# PWM.net
KiCad netlist of a schematic drawn in EAGLE
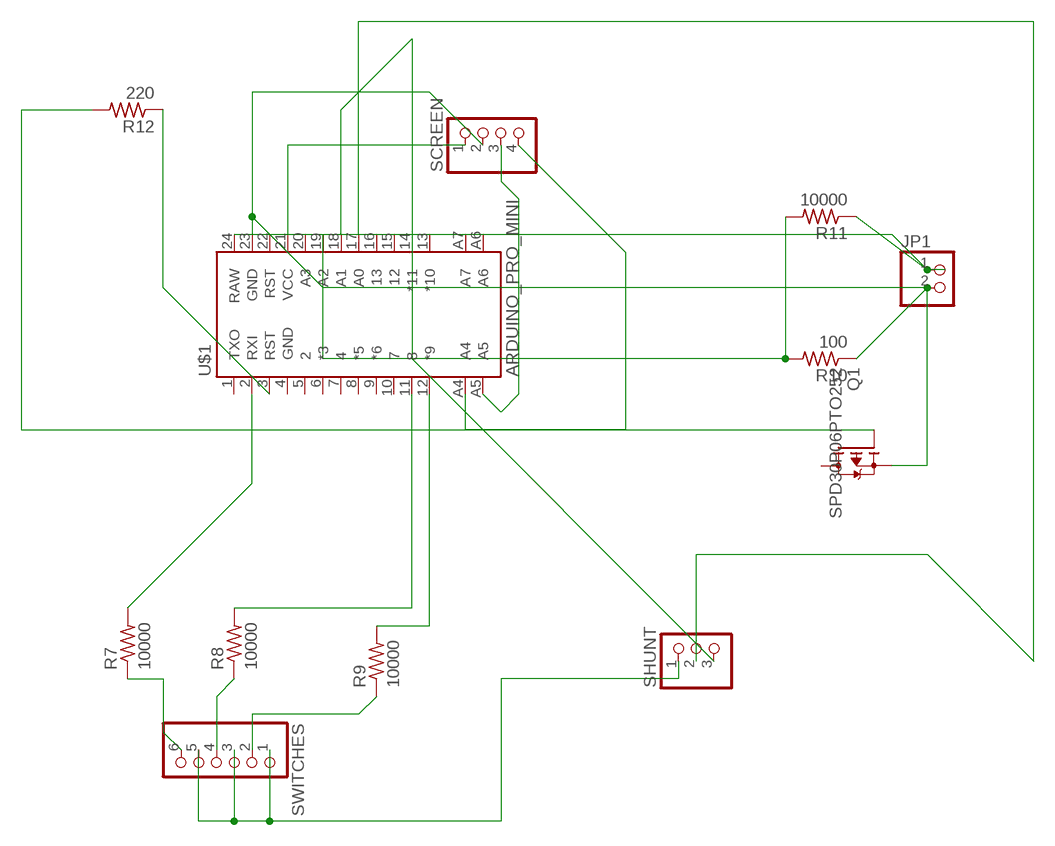
[diagram p0: schematic, sheet 1]

(export (version "E")
  (design (tool "Eeschema 10.0.6"))
  (components
    (comp (ref "JP1")
      (value "PINHD-1X2")
      (footprint "eagle-import:1X02")
      (libsource (lib "eagle-import") (part "PINHD-1X2"))
    )
    (comp (ref "Q1")
      (value "SPD30P06PTO252")
      (footprint "eagle-import:TO252")
      (libsource (lib "eagle-import") (part "SPD30P06PTO252"))
    )
    (comp (ref "R7")
      (value "10000")
      (footprint "eagle-import:0204_7")
      (libsource (lib "eagle-import") (part "R-US_0204/7"))
    )
    (comp (ref "R8")
      (value "10000")
      (footprint "eagle-import:0204_7")
      (libsource (lib "eagle-import") (part "R-US_0204/7"))
    )
    (comp (ref "R9")
      (value "10000")
      (footprint "eagle-import:0204_7")
      (libsource (lib "eagle-import") (part "R-US_0204/7"))
    )
    (comp (ref "R10")
      (value "100")
      (footprint "eagle-import:0204_7")
      (libsource (lib "eagle-import") (part "R-US_0204/7"))
    )
    (comp (ref "R11")
      (value "10000")
      (footprint "eagle-import:0204_7")
      (libsource (lib "eagle-import") (part "R-US_0204/7"))
    )
    (comp (ref "R12")
      (value "220")
      (footprint "eagle-import:0204_7")
      (libsource (lib "eagle-import") (part "R-US_0204/7"))
    )
    (comp (ref "SCREEN")
      (value "PINHD-1X4")
      (footprint "eagle-import:1X04")
      (libsource (lib "eagle-import") (part "PINHD-1X4"))
    )
    (comp (ref "SHUNT")
      (value "PINHD-1X3")
      (footprint "eagle-import:1X03")
      (libsource (lib "eagle-import") (part "PINHD-1X3"))
    )
    (comp (ref "SWITCHES")
      (value "PINHD-1X6")
      (footprint "eagle-import:1X06")
      (libsource (lib "eagle-import") (part "PINHD-1X6"))
    )
    (comp (ref "U$1")
      (value "ARDUINO_PRO_MINI")
      (footprint "eagle-import:ARDUINO_PRO_MINI")
      (libsource (lib "eagle-import") (part "ARDUINO_PRO_MINI"))
    )
  )
  (nets
    (net (code "1") (name "/2") (class "Default")
      (node (ref "R7") (pin "1") (pinfunction "1_1") (pintype "passive"))
      (node (ref "R7") (pin "2") (pinfunction "2_2") (pintype "passive"))
      (node (ref "SWITCHES") (pin "6") (pinfunction "6_6") (pintype "passive"))
      (node (ref "U$1") (pin "2") (pinfunction "RXI_2") (pintype "bidirectional"))
    )
    (net (code "2") (name "/GND") (class "Default")
      (node (ref "JP1") (pin "2") (pinfunction "2_2") (pintype "passive"))
      (node (ref "Q1") (pin "2") (pinfunction "S_2") (pintype "passive"))
      (node (ref "R10") (pin "1") (pinfunction "1_1") (pintype "passive"))
      (node (ref "SCREEN") (pin "2") (pinfunction "2_2") (pintype "passive"))
      (node (ref "SHUNT") (pin "1") (pinfunction "1_1") (pintype "passive"))
      (node (ref "SWITCHES") (pin "1") (pinfunction "1_1") (pintype "passive"))
      (node (ref "SWITCHES") (pin "3") (pinfunction "3_3") (pintype "passive"))
      (node (ref "SWITCHES") (pin "5") (pinfunction "5_5") (pintype "passive"))
      (node (ref "U$1") (pin "23") (pinfunction "GND_23") (pintype "bidirectional"))
    )
    (net (code "3") (name "Net-(Q1-G)") (class "Default")
      (node (ref "Q1") (pin "1") (pinfunction "G_1") (pintype "passive"))
      (node (ref "R12") (pin "2") (pinfunction "2_2") (pintype "passive"))
    )
    (net (code "4") (name "Net-(R8-Pad1)") (class "Default")
      (node (ref "R8") (pin "1") (pinfunction "1_1") (pintype "passive"))
      (node (ref "SWITCHES") (pin "4") (pinfunction "4_4") (pintype "passive"))
    )
    (net (code "5") (name "Net-(R9-Pad1)") (class "Default")
      (node (ref "R9") (pin "1") (pinfunction "1_1") (pintype "passive"))
      (node (ref "SWITCHES") (pin "2") (pinfunction "2_2") (pintype "passive"))
    )
    (net (code "6") (name "Net-(R12-Pad1)") (class "Default")
      (node (ref "R12") (pin "1") (pinfunction "1_1") (pintype "passive"))
      (node (ref "U$1") (pin "3") (pinfunction "RST_3") (pintype "bidirectional"))
    )
    (net (code "7") (name "Net-(SCREEN-Pad3)") (class "Default")
      (node (ref "SCREEN") (pin "3") (pinfunction "3_3") (pintype "passive"))
      (node (ref "U$1") (pin "A5") (pinfunction "A5_A5") (pintype "bidirectional"))
    )
    (net (code "8") (name "Net-(SCREEN-Pad4)") (class "Default")
      (node (ref "SCREEN") (pin "4") (pinfunction "4_4") (pintype "passive"))
      (node (ref "U$1") (pin "A4") (pinfunction "A4_A4") (pintype "bidirectional"))
    )
    (net (code "9") (name "Net-(U$1-*9)") (class "Default")
      (node (ref "R9") (pin "2") (pinfunction "2_2") (pintype "passive"))
      (node (ref "U$1") (pin "12") (pinfunction "*9_12") (pintype "bidirectional"))
    )
    (net (code "10") (name "Net-(U$1-8)") (class "Default")
      (node (ref "R8") (pin "2") (pinfunction "2_2") (pintype "passive"))
      (node (ref "U$1") (pin "11") (pinfunction "8_11") (pintype "bidirectional"))
    )
    (net (code "11") (name "Net-(U$1-A0)") (class "Default")
      (node (ref "SHUNT") (pin "2") (pinfunction "2_2") (pintype "passive"))
      (node (ref "U$1") (pin "17") (pinfunction "A0_17") (pintype "bidirectional"))
    )
    (net (code "12") (name "Net-(U$1-A1)") (class "Default")
      (node (ref "SHUNT") (pin "3") (pinfunction "3_3") (pintype "passive"))
      (node (ref "U$1") (pin "18") (pinfunction "A1_18") (pintype "bidirectional"))
    )
    (net (code "13") (name "Net-(U$1-A2)") (class "Default")
      (node (ref "R10") (pin "2") (pinfunction "2_2") (pintype "passive"))
      (node (ref "R11") (pin "2") (pinfunction "2_2") (pintype "passive"))
      (node (ref "U$1") (pin "19") (pinfunction "A2_19") (pintype "bidirectional"))
    )
    (net (code "14") (name "Net-(U$1-RAW)") (class "Default")
      (node (ref "JP1") (pin "1") (pinfunction "1_1") (pintype "passive"))
      (node (ref "R11") (pin "1") (pinfunction "1_1") (pintype "passive"))
      (node (ref "U$1") (pin "24") (pinfunction "RAW_24") (pintype "bidirectional"))
    )
    (net (code "15") (name "Net-(U$1-VCC)") (class "Default")
      (node (ref "SCREEN") (pin "1") (pinfunction "1_1") (pintype "passive"))
      (node (ref "U$1") (pin "21") (pinfunction "VCC_21") (pintype "bidirectional"))
    )
    (net (code "16") (name "unconnected-(Q1-D-Pad3)") (class "Default")
      (node (ref "Q1") (pin "3") (pinfunction "D_3") (pintype "passive"))
    )
    (net (code "17") (name "unconnected-(U$1-*3-Pad6)") (class "Default")
      (node (ref "U$1") (pin "6") (pinfunction "*3_6") (pintype "bidirectional"))
    )
    (net (code "18") (name "unconnected-(U$1-*5-Pad8)") (class "Default")
      (node (ref "U$1") (pin "8") (pinfunction "*5_8") (pintype "bidirectional"))
    )
    (net (code "19") (name "unconnected-(U$1-*6-Pad9)") (class "Default")
      (node (ref "U$1") (pin "9") (pinfunction "*6_9") (pintype "bidirectional"))
    )
    (net (code "20") (name "unconnected-(U$1-*10-Pad13)") (class "Default")
      (node (ref "U$1") (pin "13") (pinfunction "*10_13") (pintype "bidirectional"))
    )
    (net (code "21") (name "unconnected-(U$1-*11-Pad14)") (class "Default")
      (node (ref "U$1") (pin "14") (pinfunction "*11_14") (pintype "bidirectional"))
    )
    (net (code "22") (name "unconnected-(U$1-2-Pad5)") (class "Default")
      (node (ref "U$1") (pin "5") (pinfunction "2_5") (pintype "bidirectional"))
    )
    (net (code "23") (name "unconnected-(U$1-4-Pad7)") (class "Default")
      (node (ref "U$1") (pin "7") (pinfunction "4_7") (pintype "bidirectional"))
    )
    (net (code "24") (name "unconnected-(U$1-7-Pad10)") (class "Default")
      (node (ref "U$1") (pin "10") (pinfunction "7_10") (pintype "bidirectional"))
    )
    (net (code "25") (name "unconnected-(U$1-12-Pad15)") (class "Default")
      (node (ref "U$1") (pin "15") (pinfunction "12_15") (pintype "bidirectional"))
    )
    (net (code "26") (name "unconnected-(U$1-13-Pad16)") (class "Default")
      (node (ref "U$1") (pin "16") (pinfunction "13_16") (pintype "bidirectional"))
    )
    (net (code "27") (name "unconnected-(U$1-A3-Pad20)") (class "Default")
      (node (ref "U$1") (pin "20") (pinfunction "A3_20") (pintype "bidirectional"))
    )
    (net (code "28") (name "unconnected-(U$1-GND-Pad4)") (class "Default")
      (node (ref "U$1") (pin "4") (pinfunction "GND_4") (pintype "bidirectional"))
    )
    (net (code "29") (name "unconnected-(U$1-PadA6)") (class "Default")
      (node (ref "U$1") (pin "A6") (pinfunction "A6_A6") (pintype "bidirectional"))
    )
    (net (code "30") (name "unconnected-(U$1-PadA7)") (class "Default")
      (node (ref "U$1") (pin "A7") (pinfunction "A7_A7") (pintype "bidirectional"))
    )
    (net (code "31") (name "unconnected-(U$1-RST-Pad22)") (class "Default")
      (node (ref "U$1") (pin "22") (pinfunction "RST_22") (pintype "bidirectional"))
    )
    (net (code "32") (name "unconnected-(U$1-TXO-Pad1)") (class "Default")
      (node (ref "U$1") (pin "1") (pinfunction "TXO_1") (pintype "bidirectional"))
    )
  )
)
